# EE194_YESDIG_PCB.net
KiCad netlist of a schematic drawn in Altium Designer
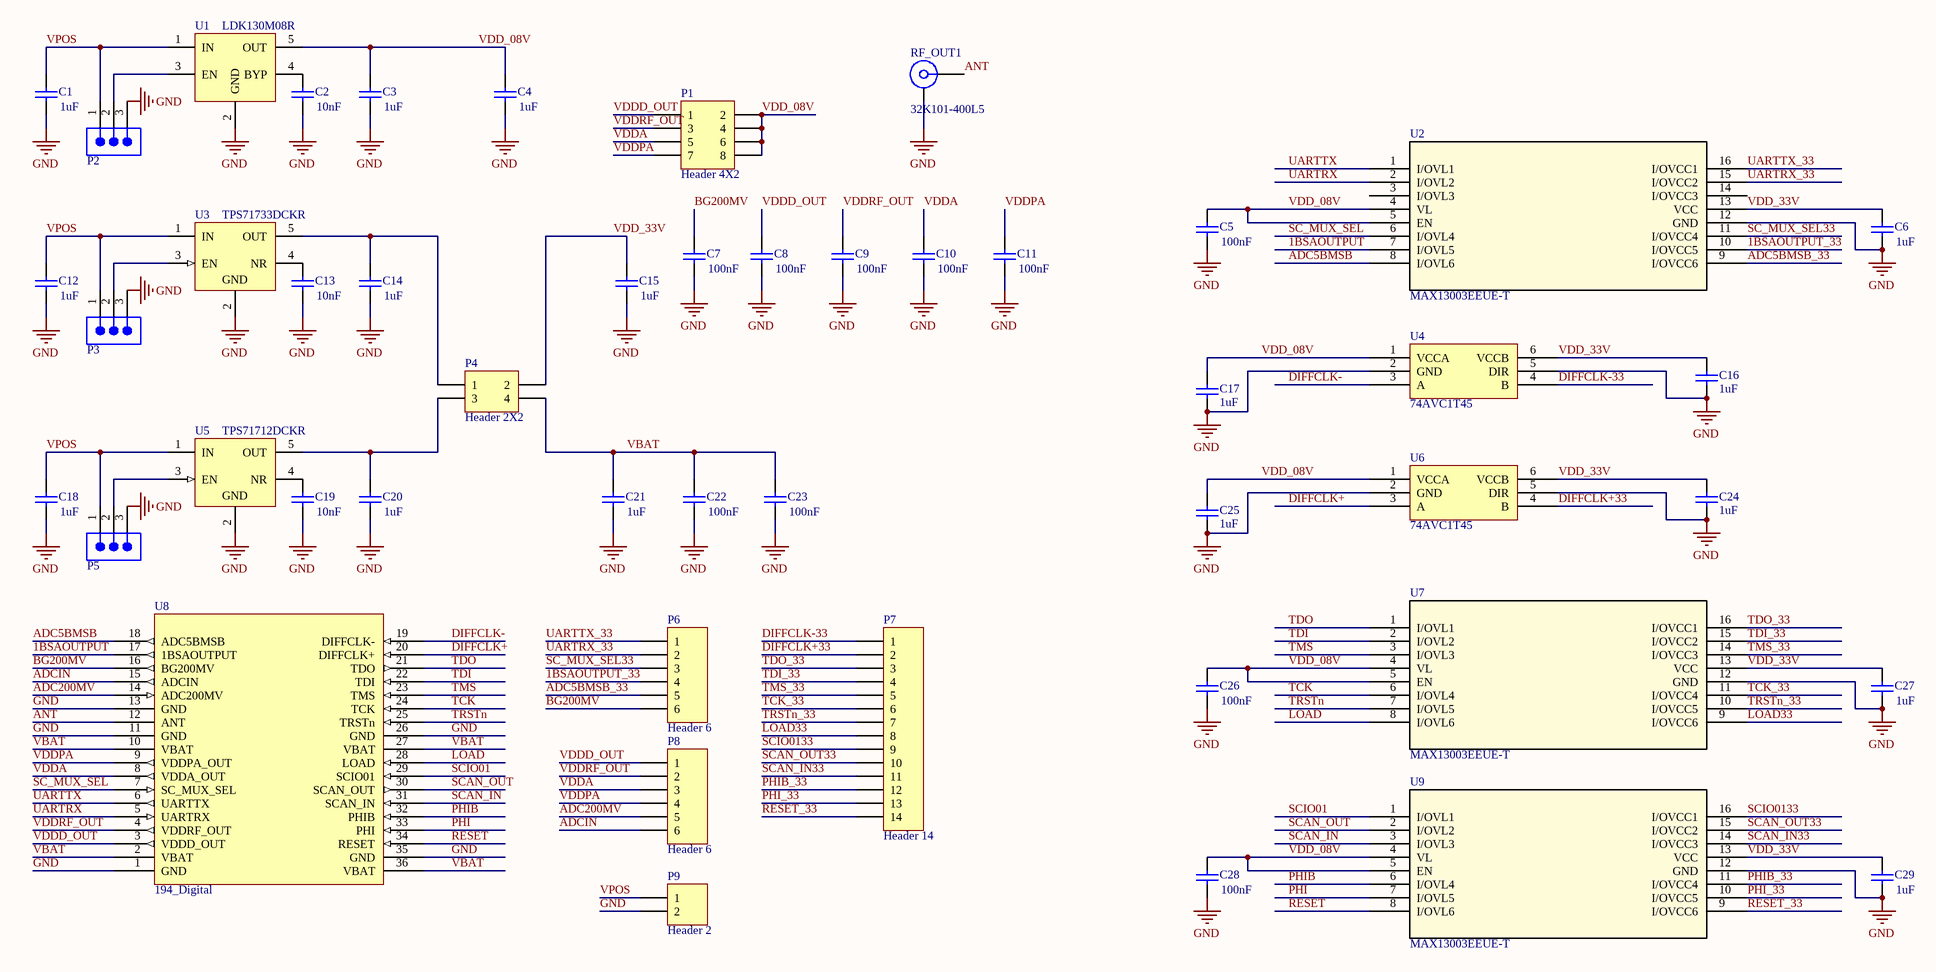
[diagram p0: EE194_YESDIG_PCB.SchDoc]

(export (version "E")
  (design (tool "Eeschema 10.0.6"))
  (components
    (comp (ref "C1")
      (value "1uF")
      (footprint "1608[0603]")
      (description "Capacitor (Semiconductor SIM Model)")
      (fields (field (name "Comment") "Cap Semi") (field (name "PUBLISHER") "Altium Limited"))
      (libsource (lib "Miscellaneous Devices") (part "Cap Semi"))
    )
    (comp (ref "C2")
      (value "10nF")
      (footprint "1608[0603]")
      (description "Capacitor (Semiconductor SIM Model)")
      (fields (field (name "Comment") "Cap Semi") (field (name "PUBLISHER") "Altium Limited"))
      (libsource (lib "Miscellaneous Devices") (part "Cap Semi"))
    )
    (comp (ref "C3")
      (value "1uF")
      (footprint "1608[0603]")
      (description "Capacitor (Semiconductor SIM Model)")
      (fields (field (name "Comment") "Cap Semi") (field (name "PUBLISHER") "Altium Limited"))
      (libsource (lib "Miscellaneous Devices") (part "Cap Semi"))
    )
    (comp (ref "C4")
      (value "1uF")
      (footprint "1608[0603]")
      (description "Capacitor (Semiconductor SIM Model)")
      (fields (field (name "Comment") "Cap Semi") (field (name "PUBLISHER") "Altium Limited"))
      (libsource (lib "Miscellaneous Devices") (part "Cap Semi"))
    )
    (comp (ref "C5")
      (value "100nF")
      (footprint "0402")
      (description "Capacitor (Semiconductor SIM Model)")
      (fields (field (name "Comment") "Cap Semi") (field (name "PUBLISHER") "Altium Limited"))
      (libsource (lib "Miscellaneous Devices") (part "Cap Semi"))
    )
    (comp (ref "C6")
      (value "1uF")
      (footprint "0402")
      (description "Capacitor (Semiconductor SIM Model)")
      (fields (field (name "Comment") "Cap Semi") (field (name "PUBLISHER") "Altium Limited"))
      (libsource (lib "Miscellaneous Devices") (part "Cap Semi"))
    )
    (comp (ref "C7")
      (value "100nF")
      (footprint "0402")
      (description "Capacitor (Semiconductor SIM Model)")
      (fields (field (name "Comment") "Cap Semi") (field (name "PUBLISHER") "Altium Limited"))
      (libsource (lib "Miscellaneous Devices") (part "Cap Semi"))
    )
    (comp (ref "C8")
      (value "100nF")
      (footprint "0402")
      (description "Capacitor (Semiconductor SIM Model)")
      (fields (field (name "Comment") "Cap Semi") (field (name "PUBLISHER") "Altium Limited"))
      (libsource (lib "Miscellaneous Devices") (part "Cap Semi"))
    )
    (comp (ref "C9")
      (value "100nF")
      (footprint "0402")
      (description "Capacitor (Semiconductor SIM Model)")
      (fields (field (name "Comment") "Cap Semi") (field (name "PUBLISHER") "Altium Limited"))
      (libsource (lib "Miscellaneous Devices") (part "Cap Semi"))
    )
    (comp (ref "C10")
      (value "100nF")
      (footprint "0402")
      (description "Capacitor (Semiconductor SIM Model)")
      (fields (field (name "Comment") "Cap Semi") (field (name "PUBLISHER") "Altium Limited"))
      (libsource (lib "Miscellaneous Devices") (part "Cap Semi"))
    )
    (comp (ref "C11")
      (value "100nF")
      (footprint "0402")
      (description "Capacitor (Semiconductor SIM Model)")
      (fields (field (name "Comment") "Cap Semi") (field (name "PUBLISHER") "Altium Limited"))
      (libsource (lib "Miscellaneous Devices") (part "Cap Semi"))
    )
    (comp (ref "C12")
      (value "1uF")
      (footprint "1608[0603]")
      (description "Capacitor (Semiconductor SIM Model)")
      (fields (field (name "Comment") "Cap Semi") (field (name "PUBLISHER") "Altium Limited"))
      (libsource (lib "Miscellaneous Devices") (part "Cap Semi"))
    )
    (comp (ref "C13")
      (value "10nF")
      (footprint "1608[0603]")
      (description "Capacitor (Semiconductor SIM Model)")
      (fields (field (name "Comment") "Cap Semi") (field (name "PUBLISHER") "Altium Limited"))
      (libsource (lib "Miscellaneous Devices") (part "Cap Semi"))
    )
    (comp (ref "C14")
      (value "1uF")
      (footprint "1608[0603]")
      (description "Capacitor (Semiconductor SIM Model)")
      (fields (field (name "Comment") "Cap Semi") (field (name "PUBLISHER") "Altium Limited"))
      (libsource (lib "Miscellaneous Devices") (part "Cap Semi"))
    )
    (comp (ref "C15")
      (value "1uF")
      (footprint "1608[0603]")
      (description "Capacitor (Semiconductor SIM Model)")
      (fields (field (name "Comment") "Cap Semi") (field (name "PUBLISHER") "Altium Limited"))
      (libsource (lib "Miscellaneous Devices") (part "Cap Semi"))
    )
    (comp (ref "C16")
      (value "1uF")
      (footprint "CAPC0402(1005)60_M")
      (description "CAP 1uF 16V ±10% 0402 (1005 Metric) Thickness 0.6mm SMD")
      (fields (field (name "TOLERANCE") "Â±10%") (field (name "Comment") "CAP 1uF 16V 0402(1005)"))
      (libsource (lib "Altium Content Vault") (part "CMP-1034-02119-1"))
    )
    (comp (ref "C17")
      (value "1uF")
      (footprint "CAPC0402(1005)60_M")
      (description "CAP 1uF 16V ±10% 0402 (1005 Metric) Thickness 0.6mm SMD")
      (fields (field (name "TOLERANCE") "Â±10%") (field (name "Comment") "CAP 1uF 16V 0402(1005)"))
      (libsource (lib "Altium Content Vault") (part "CMP-1034-02119-1"))
    )
    (comp (ref "C18")
      (value "1uF")
      (footprint "1608[0603]")
      (description "Capacitor (Semiconductor SIM Model)")
      (fields (field (name "Comment") "Cap Semi") (field (name "PUBLISHER") "Altium Limited"))
      (libsource (lib "Miscellaneous Devices") (part "Cap Semi"))
    )
    (comp (ref "C19")
      (value "10nF")
      (footprint "1608[0603]")
      (description "Capacitor (Semiconductor SIM Model)")
      (fields (field (name "Comment") "Cap Semi") (field (name "PUBLISHER") "Altium Limited"))
      (libsource (lib "Miscellaneous Devices") (part "Cap Semi"))
    )
    (comp (ref "C20")
      (value "1uF")
      (footprint "1608[0603]")
      (description "Capacitor (Semiconductor SIM Model)")
      (fields (field (name "Comment") "Cap Semi") (field (name "PUBLISHER") "Altium Limited"))
      (libsource (lib "Miscellaneous Devices") (part "Cap Semi"))
    )
    (comp (ref "C21")
      (value "1uF")
      (footprint "1608[0603]")
      (description "Capacitor (Semiconductor SIM Model)")
      (fields (field (name "Comment") "Cap Semi") (field (name "PUBLISHER") "Altium Limited"))
      (libsource (lib "Miscellaneous Devices") (part "Cap Semi"))
    )
    (comp (ref "C22")
      (value "100nF")
      (footprint "0402")
      (description "Capacitor (Semiconductor SIM Model)")
      (fields (field (name "Comment") "Cap Semi") (field (name "PUBLISHER") "Altium Limited"))
      (libsource (lib "Miscellaneous Devices") (part "Cap Semi"))
    )
    (comp (ref "C23")
      (value "100nF")
      (footprint "0402")
      (description "Capacitor (Semiconductor SIM Model)")
      (fields (field (name "Comment") "Cap Semi") (field (name "PUBLISHER") "Altium Limited"))
      (libsource (lib "Miscellaneous Devices") (part "Cap Semi"))
    )
    (comp (ref "C24")
      (value "1uF")
      (footprint "CAPC0402(1005)60_M")
      (description "CAP 1uF 16V ±10% 0402 (1005 Metric) Thickness 0.6mm SMD")
      (fields (field (name "TOLERANCE") "Â±10%") (field (name "Comment") "CAP 1uF 16V 0402(1005)"))
      (libsource (lib "Altium Content Vault") (part "CMP-1034-02119-1"))
    )
    (comp (ref "C25")
      (value "1uF")
      (footprint "CAPC0402(1005)60_M")
      (description "CAP 1uF 16V ±10% 0402 (1005 Metric) Thickness 0.6mm SMD")
      (fields (field (name "TOLERANCE") "Â±10%") (field (name "Comment") "CAP 1uF 16V 0402(1005)"))
      (libsource (lib "Altium Content Vault") (part "CMP-1034-02119-1"))
    )
    (comp (ref "C26")
      (value "100nF")
      (footprint "0402")
      (description "Capacitor (Semiconductor SIM Model)")
      (fields (field (name "Comment") "Cap Semi") (field (name "PUBLISHER") "Altium Limited"))
      (libsource (lib "Miscellaneous Devices") (part "Cap Semi"))
    )
    (comp (ref "C27")
      (value "1uF")
      (footprint "0402")
      (description "Capacitor (Semiconductor SIM Model)")
      (fields (field (name "Comment") "Cap Semi") (field (name "PUBLISHER") "Altium Limited"))
      (libsource (lib "Miscellaneous Devices") (part "Cap Semi"))
    )
    (comp (ref "C28")
      (value "100nF")
      (footprint "0402")
      (description "Capacitor (Semiconductor SIM Model)")
      (fields (field (name "Comment") "Cap Semi") (field (name "PUBLISHER") "Altium Limited"))
      (libsource (lib "Miscellaneous Devices") (part "Cap Semi"))
    )
    (comp (ref "C29")
      (value "1uF")
      (footprint "0402")
      (description "Capacitor (Semiconductor SIM Model)")
      (fields (field (name "Comment") "Cap Semi") (field (name "PUBLISHER") "Altium Limited"))
      (libsource (lib "Miscellaneous Devices") (part "Cap Semi"))
    )
    (comp (ref "P1")
      (value "Header 4X2")
      (footprint "HDR2X4")
      (description "Header, 4-Pin, Dual row")
      (fields (field (name "PUBLISHER") "Altium Limited"))
      (libsource (lib "Miscellaneous Connectors") (part "Header 4X2"))
    )
    (comp (ref "P2")
      (value "TSW-103-07-F-S")
      (footprint "SMTC-TSW-103-07-X-S")
      (description "0.025\" SQ Post Header, Through-hole, Vertical, -55 to 125 degC, 2.54 mm Pitch, 3-Pin, Male, RoHS")
      (fields (field (name "MANUFACTURER") "Samtec"))
      (libsource (lib "Altium Content Vault") (part "SMTC-TSW-103-X-X-S-X"))
    )
    (comp (ref "P3")
      (value "TSW-103-07-F-S")
      (footprint "SMTC-TSW-103-07-X-S")
      (description "0.025\" SQ Post Header, Through-hole, Vertical, -55 to 125 degC, 2.54 mm Pitch, 3-Pin, Male, RoHS")
      (fields (field (name "MANUFACTURER") "Samtec"))
      (libsource (lib "Altium Content Vault") (part "SMTC-TSW-103-X-X-S-X"))
    )
    (comp (ref "P4")
      (value "Header 2X2")
      (footprint "HDR2X2")
      (description "Header, 2-Pin, Dual row")
      (fields (field (name "PUBLISHER") "Altium Limited"))
      (libsource (lib "Miscellaneous Connectors") (part "Header 2X2"))
    )
    (comp (ref "P5")
      (value "TSW-103-07-F-S")
      (footprint "SMTC-TSW-103-07-X-S")
      (description "0.025\" SQ Post Header, Through-hole, Vertical, -55 to 125 degC, 2.54 mm Pitch, 3-Pin, Male, RoHS")
      (fields (field (name "MANUFACTURER") "Samtec"))
      (libsource (lib "Altium Content Vault") (part "SMTC-TSW-103-X-X-S-X"))
    )
    (comp (ref "P6")
      (value "Header 6")
      (footprint "HDR1X6")
      (description "Header, 6-Pin")
      (fields (field (name "PUBLISHER") "Altium Limited"))
      (libsource (lib "Miscellaneous Connectors") (part "Header 6"))
    )
    (comp (ref "P7")
      (value "Header 14")
      (footprint "HDR1X14")
      (description "Header, 14-Pin")
      (fields (field (name "PUBLISHER") "Altium Limited"))
      (libsource (lib "Miscellaneous Connectors") (part "Header 14"))
    )
    (comp (ref "P8")
      (value "Header 6")
      (footprint "HDR1X6")
      (description "Header, 6-Pin")
      (fields (field (name "PUBLISHER") "Altium Limited"))
      (libsource (lib "Miscellaneous Connectors") (part "Header 6"))
    )
    (comp (ref "P9")
      (value "Header 2")
      (footprint "HDR1X2")
      (description "Header, 2-Pin")
      (fields (field (name "PUBLISHER") "Altium Limited"))
      (libsource (lib "Miscellaneous Connectors") (part "Header 2"))
    )
    (comp (ref "RF_OUT1")
      (value "32K101-400L5")
      (footprint "ROS-32K101-400L5_V")
      (description "SMA Straight Jack, Up to 18 GHz, -55 to 155 degC")
      (fields (field (name "MANUFACTURER") "Rosenberger"))
      (libsource (lib "Altium Content Vault") (part "ROS-CN-1F-RF1"))
    )
    (comp (ref "U1")
      (value "LDK130M08R")
      (footprint "SOT95P290X145-5N")
      (description "300 mA low quiescent current very low noise LDO (800mV)")
      (libsource (lib "EE194_PCB") (part "LDK130M08R"))
    )
    (comp (ref "U2")
      (value "MAX13003EEUE-T")
      (footprint "21-0066J_16")
      (description "Imported")
      (libsource (lib "EE194_PCB") (part "MAX13003EEUE-T"))
    )
    (comp (ref "U3")
      (value "TPS71733DCKR")
      (footprint "DCK0005A_L")
      (fields (field (name "PARTNUMBER") "TPS71712DCKR") (field (name "MANUFACTURER") "Texas Instruments"))
      (libsource (lib "EE194_PCB") (part "TI-TPS79NXX-YYSOT5"))
    )
    (comp (ref "U4")
      (value "74AVC1T45")
      (footprint "ONSC-SC-88-6-419B-02_L")
      (libsource (lib "SCuMv2-parts") (part "74AVC1T45"))
    )
    (comp (ref "U5")
      (value "TPS71712DCKR")
      (footprint "DCK0005A_L")
      (fields (field (name "MANUFACTURER") "Texas Instruments"))
      (libsource (lib "EE194_PCB") (part "TI-TPS79NXX-YYSOT5"))
    )
    (comp (ref "U6")
      (value "74AVC1T45")
      (footprint "ONSC-SC-88-6-419B-02_L")
      (libsource (lib "SCuMv2-parts") (part "74AVC1T45"))
    )
    (comp (ref "U7")
      (value "MAX13003EEUE-T")
      (footprint "21-0066J_16")
      (description "Imported")
      (libsource (lib "EE194_PCB") (part "MAX13003EEUE-T"))
    )
    (comp (ref "U8")
      (value "194_Digital")
      (footprint "EE194_Analog_Chip - 3 mil")
      (libsource (lib "EE194_PCB") (part "194_Digital"))
    )
    (comp (ref "U9")
      (value "MAX13003EEUE-T")
      (footprint "21-0066J_16")
      (description "Imported")
      (libsource (lib "EE194_PCB") (part "MAX13003EEUE-T"))
    )
  )
  (nets
    (net (code "1") (name "/1BSAOUTPUT") (class "Default")
      (node (ref "U2") (pin "7") (pinfunction "I/OVL5_7") (pintype "passive"))
      (node (ref "U8") (pin "17") (pinfunction "1BSAOUTPUT_17") (pintype "output"))
    )
    (net (code "2") (name "/1BSAOUTPUT_33") (class "Default")
      (node (ref "P6") (pin "4") (pinfunction "4_4") (pintype "passive"))
      (node (ref "U2") (pin "10") (pinfunction "I/OVCC5_10") (pintype "passive"))
    )
    (net (code "3") (name "/ADC5BMSB") (class "Default")
      (node (ref "U2") (pin "8") (pinfunction "I/OVL6_8") (pintype "passive"))
      (node (ref "U8") (pin "18") (pinfunction "ADC5BMSB_18") (pintype "output"))
    )
    (net (code "4") (name "/ADC5BMSB_33") (class "Default")
      (node (ref "P6") (pin "5") (pinfunction "5_5") (pintype "passive"))
      (node (ref "U2") (pin "9") (pinfunction "I/OVCC6_9") (pintype "passive"))
    )
    (net (code "5") (name "/ADC200MV") (class "Default")
      (node (ref "P8") (pin "5") (pinfunction "5_5") (pintype "passive"))
      (node (ref "U8") (pin "14") (pinfunction "ADC200MV_14") (pintype "input"))
    )
    (net (code "6") (name "/ADCIN") (class "Default")
      (node (ref "P8") (pin "6") (pinfunction "6_6") (pintype "passive"))
      (node (ref "U8") (pin "15") (pinfunction "ADCIN_15") (pintype "output"))
    )
    (net (code "7") (name "/ANT") (class "Default")
      (node (ref "RF_OUT1") (pin "1") (pinfunction "1_1") (pintype "passive"))
      (node (ref "U8") (pin "12") (pinfunction "ANT_12") (pintype "passive"))
    )
    (net (code "8") (name "/BG200MV") (class "Default")
      (node (ref "C7") (pin "2") (pinfunction "2_2") (pintype "passive"))
      (node (ref "P6") (pin "6") (pinfunction "6_6") (pintype "passive"))
      (node (ref "U8") (pin "16") (pinfunction "BG200MV_16") (pintype "output"))
    )
    (net (code "9") (name "/DIFFCLK+") (class "Default")
      (node (ref "U6") (pin "3") (pinfunction "A_3") (pintype "passive"))
      (node (ref "U8") (pin "20") (pinfunction "DIFFCLK+_20") (pintype "input"))
    )
    (net (code "10") (name "/DIFFCLK+33") (class "Default")
      (node (ref "P7") (pin "2") (pinfunction "2_2") (pintype "passive"))
      (node (ref "U6") (pin "4") (pinfunction "B_4") (pintype "passive"))
    )
    (net (code "11") (name "/DIFFCLK-") (class "Default")
      (node (ref "U4") (pin "3") (pinfunction "A_3") (pintype "passive"))
      (node (ref "U8") (pin "19") (pinfunction "DIFFCLK-_19") (pintype "input"))
    )
    (net (code "12") (name "/DIFFCLK-33") (class "Default")
      (node (ref "P7") (pin "1") (pinfunction "1_1") (pintype "passive"))
      (node (ref "U4") (pin "4") (pinfunction "B_4") (pintype "passive"))
    )
    (net (code "13") (name "/LOAD") (class "Default")
      (node (ref "U7") (pin "8") (pinfunction "I/OVL6_8") (pintype "passive"))
      (node (ref "U8") (pin "28") (pinfunction "LOAD_28") (pintype "input"))
    )
    (net (code "14") (name "/LOAD33") (class "Default")
      (node (ref "P7") (pin "8") (pinfunction "8_8") (pintype "passive"))
      (node (ref "U7") (pin "9") (pinfunction "I/OVCC6_9") (pintype "passive"))
    )
    (net (code "15") (name "/PHI") (class "Default")
      (node (ref "U8") (pin "33") (pinfunction "PHI_33") (pintype "input"))
      (node (ref "U9") (pin "7") (pinfunction "I/OVL5_7") (pintype "passive"))
    )
    (net (code "16") (name "/PHIB") (class "Default")
      (node (ref "U8") (pin "32") (pinfunction "PHIB_32") (pintype "input"))
      (node (ref "U9") (pin "6") (pinfunction "I/OVL4_6") (pintype "passive"))
    )
    (net (code "17") (name "/PHIB_33") (class "Default")
      (node (ref "P7") (pin "12") (pinfunction "12_12") (pintype "passive"))
      (node (ref "U9") (pin "11") (pinfunction "I/OVCC4_11") (pintype "passive"))
    )
    (net (code "18") (name "/PHI_33") (class "Default")
      (node (ref "P7") (pin "13") (pinfunction "13_13") (pintype "passive"))
      (node (ref "U9") (pin "10") (pinfunction "I/OVCC5_10") (pintype "passive"))
    )
    (net (code "19") (name "/RESET") (class "Default")
      (node (ref "U8") (pin "34") (pinfunction "RESET_34") (pintype "input"))
      (node (ref "U9") (pin "8") (pinfunction "I/OVL6_8") (pintype "passive"))
    )
    (net (code "20") (name "/RESET_33") (class "Default")
      (node (ref "P7") (pin "14") (pinfunction "14_14") (pintype "passive"))
      (node (ref "U9") (pin "9") (pinfunction "I/OVCC6_9") (pintype "passive"))
    )
    (net (code "21") (name "/SCAN_IN") (class "Default")
      (node (ref "U8") (pin "31") (pinfunction "SCAN_IN_31") (pintype "input"))
      (node (ref "U9") (pin "3") (pinfunction "I/OVL3_3") (pintype "passive"))
    )
    (net (code "22") (name "/SCAN_IN33") (class "Default")
      (node (ref "P7") (pin "11") (pinfunction "11_11") (pintype "passive"))
      (node (ref "U9") (pin "14") (pinfunction "I/OVCC3_14") (pintype "passive"))
    )
    (net (code "23") (name "/SCAN_OUT") (class "Default")
      (node (ref "U8") (pin "30") (pinfunction "SCAN_OUT_30") (pintype "output"))
      (node (ref "U9") (pin "2") (pinfunction "I/OVL2_2") (pintype "passive"))
    )
    (net (code "24") (name "/SCAN_OUT33") (class "Default")
      (node (ref "P7") (pin "10") (pinfunction "10_10") (pintype "passive"))
      (node (ref "U9") (pin "15") (pinfunction "I/OVCC2_15") (pintype "passive"))
    )
    (net (code "25") (name "/SCIO01") (class "Default")
      (node (ref "U8") (pin "29") (pinfunction "SCIO01_29") (pintype "input"))
      (node (ref "U9") (pin "1") (pinfunction "I/OVL1_1") (pintype "passive"))
    )
    (net (code "26") (name "/SCIO0133") (class "Default")
      (node (ref "P7") (pin "9") (pinfunction "9_9") (pintype "passive"))
      (node (ref "U9") (pin "16") (pinfunction "I/OVCC1_16") (pintype "passive"))
    )
    (net (code "27") (name "/SC_MUX_SEL") (class "Default")
      (node (ref "U2") (pin "6") (pinfunction "I/OVL4_6") (pintype "passive"))
      (node (ref "U8") (pin "7") (pinfunction "SC_MUX_SEL_7") (pintype "input"))
    )
    (net (code "28") (name "/SC_MUX_SEL33") (class "Default")
      (node (ref "P6") (pin "3") (pinfunction "3_3") (pintype "passive"))
      (node (ref "U2") (pin "11") (pinfunction "I/OVCC4_11") (pintype "passive"))
    )
    (net (code "29") (name "/TCK") (class "Default")
      (node (ref "U7") (pin "6") (pinfunction "I/OVL4_6") (pintype "passive"))
      (node (ref "U8") (pin "24") (pinfunction "TCK_24") (pintype "input"))
    )
    (net (code "30") (name "/TCK_33") (class "Default")
      (node (ref "P7") (pin "6") (pinfunction "6_6") (pintype "passive"))
      (node (ref "U7") (pin "11") (pinfunction "I/OVCC4_11") (pintype "passive"))
    )
    (net (code "31") (name "/TDI") (class "Default")
      (node (ref "U7") (pin "2") (pinfunction "I/OVL2_2") (pintype "passive"))
      (node (ref "U8") (pin "22") (pinfunction "TDI_22") (pintype "input"))
    )
    (net (code "32") (name "/TDI_33") (class "Default")
      (node (ref "P7") (pin "4") (pinfunction "4_4") (pintype "passive"))
      (node (ref "U7") (pin "15") (pinfunction "I/OVCC2_15") (pintype "passive"))
    )
    (net (code "33") (name "/TDO") (class "Default")
      (node (ref "U7") (pin "1") (pinfunction "I/OVL1_1") (pintype "passive"))
      (node (ref "U8") (pin "21") (pinfunction "TDO_21") (pintype "output"))
    )
    (net (code "34") (name "/TDO_33") (class "Default")
      (node (ref "P7") (pin "3") (pinfunction "3_3") (pintype "passive"))
      (node (ref "U7") (pin "16") (pinfunction "I/OVCC1_16") (pintype "passive"))
    )
    (net (code "35") (name "/TMS") (class "Default")
      (node (ref "U7") (pin "3") (pinfunction "I/OVL3_3") (pintype "passive"))
      (node (ref "U8") (pin "23") (pinfunction "TMS_23") (pintype "input"))
    )
    (net (code "36") (name "/TMS_33") (class "Default")
      (node (ref "P7") (pin "5") (pinfunction "5_5") (pintype "passive"))
      (node (ref "U7") (pin "14") (pinfunction "I/OVCC3_14") (pintype "passive"))
    )
    (net (code "37") (name "/TRSTn") (class "Default")
      (node (ref "U7") (pin "7") (pinfunction "I/OVL5_7") (pintype "passive"))
      (node (ref "U8") (pin "25") (pinfunction "TRSTn_25") (pintype "input"))
    )
    (net (code "38") (name "/TRSTn_33") (class "Default")
      (node (ref "P7") (pin "7") (pinfunction "7_7") (pintype "passive"))
      (node (ref "U7") (pin "10") (pinfunction "I/OVCC5_10") (pintype "passive"))
    )
    (net (code "39") (name "/UARTRX") (class "Default")
      (node (ref "U2") (pin "2") (pinfunction "I/OVL2_2") (pintype "passive"))
      (node (ref "U8") (pin "5") (pinfunction "UARTRX_5") (pintype "input"))
    )
    (net (code "40") (name "/UARTRX_33") (class "Default")
      (node (ref "P6") (pin "2") (pinfunction "2_2") (pintype "passive"))
      (node (ref "U2") (pin "15") (pinfunction "I/OVCC2_15") (pintype "passive"))
    )
    (net (code "41") (name "/UARTTX") (class "Default")
      (node (ref "U2") (pin "1") (pinfunction "I/OVL1_1") (pintype "passive"))
      (node (ref "U8") (pin "6") (pinfunction "UARTTX_6") (pintype "output"))
    )
    (net (code "42") (name "/UARTTX_33") (class "Default")
      (node (ref "P6") (pin "1") (pinfunction "1_1") (pintype "passive"))
      (node (ref "U2") (pin "16") (pinfunction "I/OVCC1_16") (pintype "passive"))
    )
    (net (code "43") (name "/VBAT") (class "Default")
      (node (ref "C21") (pin "2") (pinfunction "2_2") (pintype "passive"))
      (node (ref "C22") (pin "2") (pinfunction "2_2") (pintype "passive"))
      (node (ref "C23") (pin "2") (pinfunction "2_2") (pintype "passive"))
      (node (ref "P4") (pin "4") (pinfunction "4_4") (pintype "passive"))
      (node (ref "U8") (pin "10") (pinfunction "VBAT_10") (pintype "power_in"))
      (node (ref "U8") (pin "2") (pinfunction "VBAT_2") (pintype "power_in"))
      (node (ref "U8") (pin "27") (pinfunction "VBAT_27") (pintype "power_in"))
      (node (ref "U8") (pin "36") (pinfunction "VBAT_36") (pintype "power_in"))
    )
    (net (code "44") (name "/VDDA") (class "Default")
      (node (ref "C10") (pin "2") (pinfunction "2_2") (pintype "passive"))
      (node (ref "P1") (pin "5") (pinfunction "5_5") (pintype "passive"))
      (node (ref "P8") (pin "3") (pinfunction "3_3") (pintype "passive"))
      (node (ref "U8") (pin "8") (pinfunction "VDDA_OUT_8") (pintype "output"))
    )
    (net (code "45") (name "/VDDD_OUT") (class "Default")
      (node (ref "C8") (pin "2") (pinfunction "2_2") (pintype "passive"))
      (node (ref "P1") (pin "1") (pinfunction "1_1") (pintype "passive"))
      (node (ref "P8") (pin "1") (pinfunction "1_1") (pintype "passive"))
      (node (ref "U8") (pin "3") (pinfunction "VDDD_OUT_3") (pintype "output"))
    )
    (net (code "46") (name "/VDDPA") (class "Default")
      (node (ref "C11") (pin "2") (pinfunction "2_2") (pintype "passive"))
      (node (ref "P1") (pin "7") (pinfunction "7_7") (pintype "passive"))
      (node (ref "P8") (pin "4") (pinfunction "4_4") (pintype "passive"))
      (node (ref "U8") (pin "9") (pinfunction "VDDPA_OUT_9") (pintype "output"))
    )
    (net (code "47") (name "/VDDRF_OUT") (class "Default")
      (node (ref "C9") (pin "2") (pinfunction "2_2") (pintype "passive"))
      (node (ref "P1") (pin "3") (pinfunction "3_3") (pintype "passive"))
      (node (ref "P8") (pin "2") (pinfunction "2_2") (pintype "passive"))
      (node (ref "U8") (pin "4") (pinfunction "VDDRF_OUT_4") (pintype "output"))
    )
    (net (code "48") (name "/VDD_08V") (class "Default")
      (node (ref "C17") (pin "1") (pinfunction "1_1") (pintype "passive"))
      (node (ref "C25") (pin "1") (pinfunction "1_1") (pintype "passive"))
      (node (ref "C26") (pin "2") (pinfunction "2_2") (pintype "passive"))
      (node (ref "C28") (pin "2") (pinfunction "2_2") (pintype "passive"))
      (node (ref "C3") (pin "2") (pinfunction "2_2") (pintype "passive"))
      (node (ref "C4") (pin "2") (pinfunction "2_2") (pintype "passive"))
      (node (ref "C5") (pin "2") (pinfunction "2_2") (pintype "passive"))
      (node (ref "P1") (pin "2") (pinfunction "2_2") (pintype "passive"))
      (node (ref "P1") (pin "4") (pinfunction "4_4") (pintype "passive"))
      (node (ref "P1") (pin "6") (pinfunction "6_6") (pintype "passive"))
      (node (ref "P1") (pin "8") (pinfunction "8_8") (pintype "passive"))
      (node (ref "U1") (pin "5") (pinfunction "OUT_5") (pintype "passive"))
      (node (ref "U2") (pin "4") (pinfunction "VL_4") (pintype "power_in"))
      (node (ref "U2") (pin "5") (pinfunction "EN_5") (pintype "passive"))
      (node (ref "U4") (pin "1") (pinfunction "VCCA_1") (pintype "passive"))
      (node (ref "U6") (pin "1") (pinfunction "VCCA_1") (pintype "passive"))
      (node (ref "U7") (pin "4") (pinfunction "VL_4") (pintype "power_in"))
      (node (ref "U7") (pin "5") (pinfunction "EN_5") (pintype "passive"))
      (node (ref "U9") (pin "4") (pinfunction "VL_4") (pintype "power_in"))
      (node (ref "U9") (pin "5") (pinfunction "EN_5") (pintype "passive"))
    )
    (net (code "49") (name "/VDD_33V") (class "Default")
      (node (ref "C15") (pin "2") (pinfunction "2_2") (pintype "passive"))
      (node (ref "C16") (pin "1") (pinfunction "1_1") (pintype "passive"))
      (node (ref "C24") (pin "1") (pinfunction "1_1") (pintype "passive"))
      (node (ref "C27") (pin "2") (pinfunction "2_2") (pintype "passive"))
      (node (ref "C29") (pin "2") (pinfunction "2_2") (pintype "passive"))
      (node (ref "C6") (pin "2") (pinfunction "2_2") (pintype "passive"))
      (node (ref "P4") (pin "2") (pinfunction "2_2") (pintype "passive"))
      (node (ref "U2") (pin "13") (pinfunction "VCC_13") (pintype "power_in"))
      (node (ref "U4") (pin "6") (pinfunction "VCCB_6") (pintype "passive"))
      (node (ref "U6") (pin "6") (pinfunction "VCCB_6") (pintype "passive"))
      (node (ref "U7") (pin "13") (pinfunction "VCC_13") (pintype "power_in"))
      (node (ref "U9") (pin "13") (pinfunction "VCC_13") (pintype "power_in"))
    )
    (net (code "50") (name "/VPOS") (class "Default")
      (node (ref "C1") (pin "2") (pinfunction "2_2") (pintype "passive"))
      (node (ref "C12") (pin "2") (pinfunction "2_2") (pintype "passive"))
      (node (ref "C18") (pin "2") (pinfunction "2_2") (pintype "passive"))
      (node (ref "P2") (pin "1") (pinfunction "1_1") (pintype "passive"))
      (node (ref "P3") (pin "1") (pinfunction "1_1") (pintype "passive"))
      (node (ref "P5") (pin "1") (pinfunction "1_1") (pintype "passive"))
      (node (ref "P9") (pin "1") (pinfunction "1_1") (pintype "passive"))
      (node (ref "U1") (pin "1") (pinfunction "IN_1") (pintype "passive"))
      (node (ref "U3") (pin "1") (pinfunction "IN_1") (pintype "power_in"))
      (node (ref "U5") (pin "1") (pinfunction "IN_1") (pintype "power_in"))
    )
    (net (code "51") (name "GND") (class "Default")
      (node (ref "C1") (pin "1") (pinfunction "1_1") (pintype "passive"))
      (node (ref "C10") (pin "1") (pinfunction "1_1") (pintype "passive"))
      (node (ref "C11") (pin "1") (pinfunction "1_1") (pintype "passive"))
      (node (ref "C12") (pin "1") (pinfunction "1_1") (pintype "passive"))
      (node (ref "C13") (pin "1") (pinfunction "1_1") (pintype "passive"))
      (node (ref "C14") (pin "1") (pinfunction "1_1") (pintype "passive"))
      (node (ref "C15") (pin "1") (pinfunction "1_1") (pintype "passive"))
      (node (ref "C16") (pin "2") (pinfunction "2_2") (pintype "passive"))
      (node (ref "C17") (pin "2") (pinfunction "2_2") (pintype "passive"))
      (node (ref "C18") (pin "1") (pinfunction "1_1") (pintype "passive"))
      (node (ref "C19") (pin "1") (pinfunction "1_1") (pintype "passive"))
      (node (ref "C2") (pin "1") (pinfunction "1_1") (pintype "passive"))
      (node (ref "C20") (pin "1") (pinfunction "1_1") (pintype "passive"))
      (node (ref "C21") (pin "1") (pinfunction "1_1") (pintype "passive"))
      (node (ref "C22") (pin "1") (pinfunction "1_1") (pintype "passive"))
      (node (ref "C23") (pin "1") (pinfunction "1_1") (pintype "passive"))
      (node (ref "C24") (pin "2") (pinfunction "2_2") (pintype "passive"))
      (node (ref "C25") (pin "2") (pinfunction "2_2") (pintype "passive"))
      (node (ref "C26") (pin "1") (pinfunction "1_1") (pintype "passive"))
      (node (ref "C27") (pin "1") (pinfunction "1_1") (pintype "passive"))
      (node (ref "C28") (pin "1") (pinfunction "1_1") (pintype "passive"))
      (node (ref "C29") (pin "1") (pinfunction "1_1") (pintype "passive"))
      (node (ref "C3") (pin "1") (pinfunction "1_1") (pintype "passive"))
      (node (ref "C4") (pin "1") (pinfunction "1_1") (pintype "passive"))
      (node (ref "C5") (pin "1") (pinfunction "1_1") (pintype "passive"))
      (node (ref "C6") (pin "1") (pinfunction "1_1") (pintype "passive"))
      (node (ref "C7") (pin "1") (pinfunction "1_1") (pintype "passive"))
      (node (ref "C8") (pin "1") (pinfunction "1_1") (pintype "passive"))
      (node (ref "C9") (pin "1") (pinfunction "1_1") (pintype "passive"))
      (node (ref "P2") (pin "3") (pinfunction "3_3") (pintype "passive"))
      (node (ref "P3") (pin "3") (pinfunction "3_3") (pintype "passive"))
      (node (ref "P5") (pin "3") (pinfunction "3_3") (pintype "passive"))
      (node (ref "P9") (pin "2") (pinfunction "2_2") (pintype "passive"))
      (node (ref "RF_OUT1") (pin "MH") (pinfunction "MH_MH") (pintype "passive"))
      (node (ref "U1") (pin "2") (pinfunction "GND_2") (pintype "passive"))
      (node (ref "U2") (pin "12") (pinfunction "GND_12") (pintype "power_in"))
      (node (ref "U3") (pin "2") (pinfunction "GND_2") (pintype "power_in"))
      (node (ref "U4") (pin "2") (pinfunction "GND_2") (pintype "passive"))
      (node (ref "U4") (pin "5") (pinfunction "DIR_5") (pintype "passive"))
      (node (ref "U5") (pin "2") (pinfunction "GND_2") (pintype "power_in"))
      (node (ref "U6") (pin "2") (pinfunction "GND_2") (pintype "passive"))
      (node (ref "U6") (pin "5") (pinfunction "DIR_5") (pintype "passive"))
      (node (ref "U7") (pin "12") (pinfunction "GND_12") (pintype "power_in"))
      (node (ref "U8") (pin "1") (pinfunction "GND_1") (pintype "power_in"))
      (node (ref "U8") (pin "11") (pinfunction "GND_11") (pintype "power_in"))
      (node (ref "U8") (pin "13") (pinfunction "GND_13") (pintype "power_in"))
      (node (ref "U8") (pin "26") (pinfunction "GND_26") (pintype "power_in"))
      (node (ref "U8") (pin "35") (pinfunction "GND_35") (pintype "power_in"))
      (node (ref "U9") (pin "12") (pinfunction "GND_12") (pintype "power_in"))
    )
    (net (code "52") (name "Net-(U1-BYP)") (class "Default")
      (node (ref "C2") (pin "2") (pinfunction "2_2") (pintype "passive"))
      (node (ref "U1") (pin "4") (pinfunction "BYP_4") (pintype "passive"))
    )
    (net (code "53") (name "Net-(U1-EN)") (class "Default")
      (node (ref "P2") (pin "2") (pinfunction "2_2") (pintype "passive"))
      (node (ref "U1") (pin "3") (pinfunction "EN_3") (pintype "passive"))
    )
    (net (code "54") (name "Net-(U3-EN)") (class "Default")
      (node (ref "P3") (pin "2") (pinfunction "2_2") (pintype "passive"))
      (node (ref "U3") (pin "3") (pinfunction "EN_3") (pintype "input"))
    )
    (net (code "55") (name "Net-(U3-NR)") (class "Default")
      (node (ref "C13") (pin "2") (pinfunction "2_2") (pintype "passive"))
      (node (ref "U3") (pin "4") (pinfunction "NR_4") (pintype "passive"))
    )
    (net (code "56") (name "Net-(U3-OUT)") (class "Default")
      (node (ref "C14") (pin "2") (pinfunction "2_2") (pintype "passive"))
      (node (ref "P4") (pin "1") (pinfunction "1_1") (pintype "passive"))
      (node (ref "U3") (pin "5") (pinfunction "OUT_5") (pintype "power_in"))
    )
    (net (code "57") (name "Net-(U5-EN)") (class "Default")
      (node (ref "P5") (pin "2") (pinfunction "2_2") (pintype "passive"))
      (node (ref "U5") (pin "3") (pinfunction "EN_3") (pintype "input"))
    )
    (net (code "58") (name "Net-(U5-NR)") (class "Default")
      (node (ref "C19") (pin "2") (pinfunction "2_2") (pintype "passive"))
      (node (ref "U5") (pin "4") (pinfunction "NR_4") (pintype "passive"))
    )
    (net (code "59") (name "Net-(U5-OUT)") (class "Default")
      (node (ref "C20") (pin "2") (pinfunction "2_2") (pintype "passive"))
      (node (ref "P4") (pin "3") (pinfunction "3_3") (pintype "passive"))
      (node (ref "U5") (pin "5") (pinfunction "OUT_5") (pintype "power_in"))
    )
    (net (code "60") (name "unconnected-(U2-I{slash}OVCC3-Pad14)") (class "Default")
      (node (ref "U2") (pin "14") (pinfunction "I/OVCC3_14") (pintype "passive"))
    )
    (net (code "61") (name "unconnected-(U2-I{slash}OVL3-Pad3)") (class "Default")
      (node (ref "U2") (pin "3") (pinfunction "I/OVL3_3") (pintype "passive"))
    )
  )
)
